# MDeckProgrammer.net
KiCad netlist of a schematic drawn in EAGLE
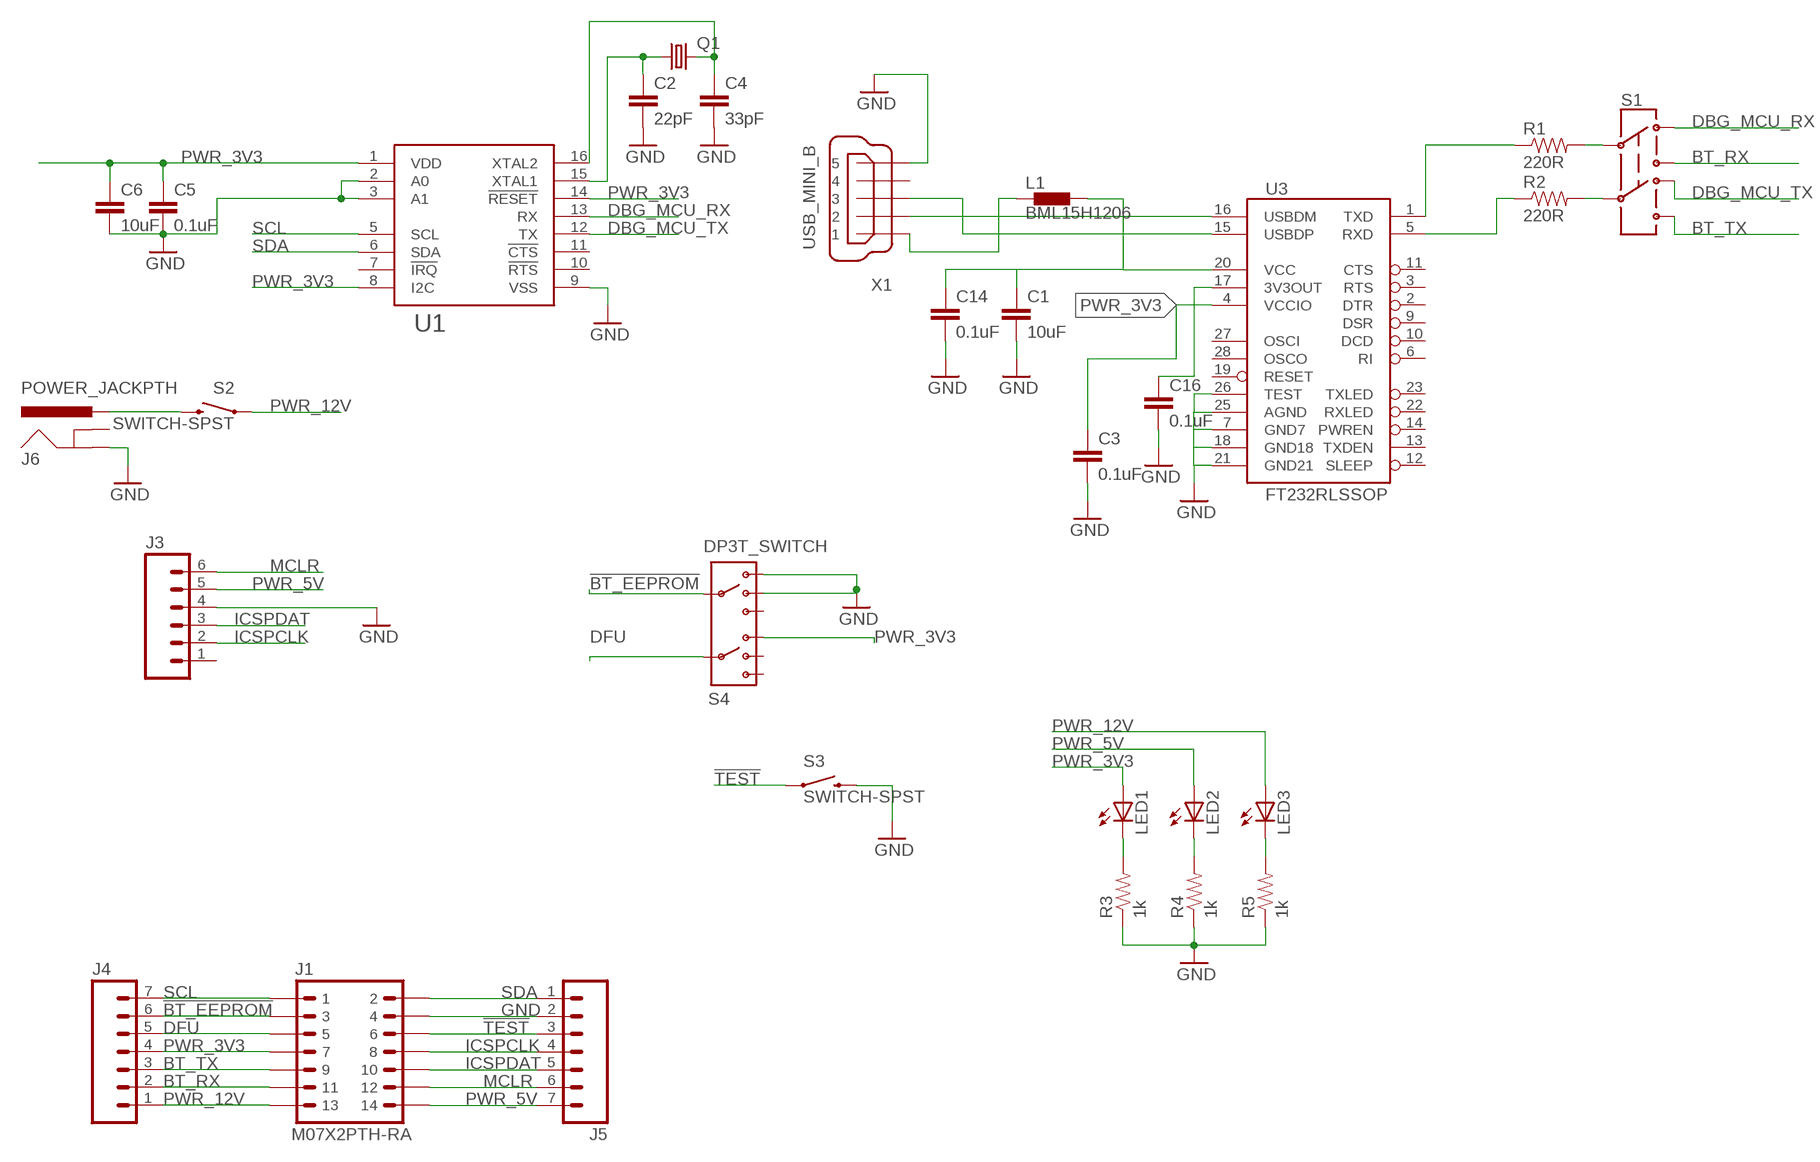
[diagram p0: schematic, sheet 1]

(export (version "E")
  (design (tool "Eeschema 10.0.6"))
  (components
    (comp (ref "C1")
      (value "10uF")
      (footprint "eagle-import:1206")
      (libsource (lib "eagle-import") (part "CAP1206"))
    )
    (comp (ref "C2")
      (value "22pF")
      (footprint "eagle-import:1206")
      (libsource (lib "eagle-import") (part "CAP1206"))
    )
    (comp (ref "C3")
      (value "0.1uF")
      (footprint "eagle-import:1206")
      (libsource (lib "eagle-import") (part "CAP1206"))
    )
    (comp (ref "C4")
      (value "33pF")
      (footprint "eagle-import:1206")
      (libsource (lib "eagle-import") (part "CAP1206"))
    )
    (comp (ref "C5")
      (value "0.1uF")
      (footprint "eagle-import:1206")
      (libsource (lib "eagle-import") (part "CAP1206"))
    )
    (comp (ref "C6")
      (value "10uF")
      (footprint "eagle-import:1206")
      (libsource (lib "eagle-import") (part "CAP1206"))
    )
    (comp (ref "C14")
      (value "0.1uF")
      (footprint "eagle-import:1206")
      (libsource (lib "eagle-import") (part "CAP1206"))
    )
    (comp (ref "C16")
      (value "0.1uF")
      (footprint "eagle-import:1206")
      (libsource (lib "eagle-import") (part "CAP1206"))
    )
    (comp (ref "J1")
      (value "M07X2PTH-RA")
      (footprint "eagle-import:JST-14-PUD-PTH")
      (libsource (lib "eagle-import") (part "M07X2PTH-RA"))
    )
    (comp (ref "J3")
      (value "M06HARWIN_RA")
      (footprint "eagle-import:1X06_RA")
      (libsource (lib "eagle-import") (part "M06HARWIN_RA"))
    )
    (comp (ref "J4")
      (value "M07")
      (footprint "eagle-import:1X07")
      (libsource (lib "eagle-import") (part "M07"))
    )
    (comp (ref "J5")
      (value "M07")
      (footprint "eagle-import:1X07")
      (libsource (lib "eagle-import") (part "M07"))
    )
    (comp (ref "J6")
      (value "POWER_JACKPTH")
      (footprint "eagle-import:POWER_JACK_PTH")
      (libsource (lib "eagle-import") (part "POWER_JACKPTH"))
    )
    (comp (ref "L1")
      (value "BML15H1206")
      (footprint "eagle-import:1206")
      (libsource (lib "eagle-import") (part "BML15H1206"))
    )
    (comp (ref "LED1")
      (value "LEDCHIPLED_1206")
      (footprint "eagle-import:CHIPLED_1206")
      (libsource (lib "eagle-import") (part "LEDCHIPLED_1206"))
    )
    (comp (ref "LED2")
      (value "LEDCHIPLED_1206")
      (footprint "eagle-import:CHIPLED_1206")
      (libsource (lib "eagle-import") (part "LEDCHIPLED_1206"))
    )
    (comp (ref "LED3")
      (value "LEDCHIPLED_1206")
      (footprint "eagle-import:CHIPLED_1206")
      (libsource (lib "eagle-import") (part "LEDCHIPLED_1206"))
    )
    (comp (ref "Q1")
      (value "CRYSTALHC49S")
      (footprint "eagle-import:HC49_S")
      (libsource (lib "eagle-import") (part "CRYSTALHC49S"))
    )
    (comp (ref "R1")
      (value "220R")
      (footprint "eagle-import:1206")
      (libsource (lib "eagle-import") (part "RESISTOR1206"))
    )
    (comp (ref "R2")
      (value "220R")
      (footprint "eagle-import:1206")
      (libsource (lib "eagle-import") (part "RESISTOR1206"))
    )
    (comp (ref "R3")
      (value "1k")
      (footprint "eagle-import:1206")
      (libsource (lib "eagle-import") (part "RESISTOR1206"))
    )
    (comp (ref "R4")
      (value "1k")
      (footprint "eagle-import:1206")
      (libsource (lib "eagle-import") (part "RESISTOR1206"))
    )
    (comp (ref "R5")
      (value "1k")
      (footprint "eagle-import:1206")
      (libsource (lib "eagle-import") (part "RESISTOR1206"))
    )
    (comp (ref "S1")
      (value "SWITCH-DPDTPTH")
      (footprint "eagle-import:MSS22")
      (libsource (lib "eagle-import") (part "SWITCH-DPDTPTH"))
    )
    (comp (ref "S2")
      (value "SWITCH-SPST")
      (footprint "eagle-import:GF-123-0054")
      (libsource (lib "eagle-import") (part "SWITCH-SPST"))
    )
    (comp (ref "S3")
      (value "SWITCH-SPST")
      (footprint "eagle-import:GF-123-0054")
      (libsource (lib "eagle-import") (part "SWITCH-SPST"))
    )
    (comp (ref "S4")
      (value "DP3T_SWITCH")
      (footprint "eagle-import:EG2301A")
      (libsource (lib "eagle-import") (part "DP3T_SWITCH"))
    )
    (comp (ref "U1")
      (value "SC16IS740TSSOP16")
      (footprint "eagle-import:TSSOP16")
      (libsource (lib "eagle-import") (part "SC16IS740TSSOP16"))
    )
    (comp (ref "U3")
      (value "FT232RLSSOP")
      (footprint "eagle-import:SSOP28DB")
      (libsource (lib "eagle-import") (part "FT232RLSSOP"))
    )
    (comp (ref "X1")
      (value "USB_MINI_B")
      (footprint "eagle-import:USB_MINI_B_PTH")
      (libsource (lib "eagle-import") (part "USB_MINI_B"))
    )
  )
  (nets
    (net (code "1") (name "/BT_RX") (class "Default")
      (node (ref "J1") (pin "P$11") (pinfunction "11_P$11") (pintype "passive"))
      (node (ref "J4") (pin "2") (pinfunction "2_2") (pintype "passive"))
      (node (ref "S1") (pin "3") (pinfunction "3_3") (pintype "bidirectional"))
    )
    (net (code "2") (name "/BT_TX") (class "Default")
      (node (ref "J1") (pin "P$9") (pinfunction "9_P$9") (pintype "passive"))
      (node (ref "J4") (pin "3") (pinfunction "3_3") (pintype "passive"))
      (node (ref "S1") (pin "6") (pinfunction "6_6") (pintype "bidirectional"))
    )
    (net (code "3") (name "/DBG_MCU_RX") (class "Default")
      (node (ref "S1") (pin "1") (pinfunction "1_1") (pintype "bidirectional"))
      (node (ref "U1") (pin "13") (pinfunction "RX_13") (pintype "bidirectional"))
    )
    (net (code "4") (name "/DBG_MCU_TX") (class "Default")
      (node (ref "S1") (pin "4") (pinfunction "4_4") (pintype "bidirectional"))
      (node (ref "U1") (pin "12") (pinfunction "TX_12") (pintype "bidirectional"))
    )
    (net (code "5") (name "/DFU") (class "Default")
      (node (ref "J1") (pin "P$5") (pinfunction "5_P$5") (pintype "passive"))
      (node (ref "J4") (pin "5") (pinfunction "5_5") (pintype "passive"))
      (node (ref "S4") (pin "P$7") (pinfunction "COMB_P$7") (pintype "passive"))
    )
    (net (code "6") (name "/ICSPCLK") (class "Default")
      (node (ref "J1") (pin "P$8") (pinfunction "8_P$8") (pintype "passive"))
      (node (ref "J3") (pin "2") (pinfunction "2_2") (pintype "passive"))
      (node (ref "J5") (pin "4") (pinfunction "4_4") (pintype "passive"))
    )
    (net (code "7") (name "/ICSPDAT") (class "Default")
      (node (ref "J1") (pin "P$10") (pinfunction "10_P$10") (pintype "passive"))
      (node (ref "J3") (pin "3") (pinfunction "3_3") (pintype "passive"))
      (node (ref "J5") (pin "5") (pinfunction "5_5") (pintype "passive"))
    )
    (net (code "8") (name "/MCLR") (class "Default")
      (node (ref "J1") (pin "P$12") (pinfunction "12_P$12") (pintype "passive"))
      (node (ref "J3") (pin "6") (pinfunction "6_6") (pintype "passive"))
      (node (ref "J5") (pin "6") (pinfunction "6_6") (pintype "passive"))
    )
    (net (code "9") (name "/PWR_5V") (class "Default")
      (node (ref "J1") (pin "P$14") (pinfunction "14_P$14") (pintype "passive"))
      (node (ref "J3") (pin "5") (pinfunction "5_5") (pintype "passive"))
      (node (ref "J5") (pin "7") (pinfunction "7_7") (pintype "passive"))
      (node (ref "LED2") (pin "A") (pinfunction "A_A") (pintype "passive"))
    )
    (net (code "10") (name "/PWR_12V") (class "Default")
      (node (ref "J1") (pin "P$13") (pinfunction "13_P$13") (pintype "passive"))
      (node (ref "J4") (pin "1") (pinfunction "1_1") (pintype "passive"))
      (node (ref "LED3") (pin "A") (pinfunction "A_A") (pintype "passive"))
      (node (ref "S2") (pin "P$1") (pinfunction "1_P$1") (pintype "passive"))
    )
    (net (code "11") (name "/SCL") (class "Default")
      (node (ref "J1") (pin "P$1") (pinfunction "1_P$1") (pintype "passive"))
      (node (ref "J4") (pin "7") (pinfunction "7_7") (pintype "passive"))
      (node (ref "U1") (pin "5") (pinfunction "SCL_5") (pintype "bidirectional"))
    )
    (net (code "12") (name "/SDA") (class "Default")
      (node (ref "J1") (pin "P$2") (pinfunction "2_P$2") (pintype "passive"))
      (node (ref "J5") (pin "1") (pinfunction "1_1") (pintype "passive"))
      (node (ref "U1") (pin "6") (pinfunction "SDA_6") (pintype "bidirectional"))
    )
    (net (code "13") (name "/~{BT_EEPROM}") (class "Default")
      (node (ref "J1") (pin "P$3") (pinfunction "3_P$3") (pintype "passive"))
      (node (ref "J4") (pin "6") (pinfunction "6_6") (pintype "passive"))
      (node (ref "S4") (pin "P$3") (pinfunction "COMA_P$3") (pintype "passive"))
    )
    (net (code "14") (name "/~{TEST}") (class "Default")
      (node (ref "J1") (pin "P$6") (pinfunction "6_P$6") (pintype "passive"))
      (node (ref "J5") (pin "3") (pinfunction "3_3") (pintype "passive"))
      (node (ref "S3") (pin "P$1") (pinfunction "1_P$1") (pintype "passive"))
    )
    (net (code "15") (name "GND") (class "Default")
      (node (ref "C1") (pin "2") (pinfunction "2_2") (pintype "passive"))
      (node (ref "C14") (pin "2") (pinfunction "2_2") (pintype "passive"))
      (node (ref "C16") (pin "2") (pinfunction "2_2") (pintype "passive"))
      (node (ref "C2") (pin "2") (pinfunction "2_2") (pintype "passive"))
      (node (ref "C3") (pin "2") (pinfunction "2_2") (pintype "passive"))
      (node (ref "C4") (pin "2") (pinfunction "2_2") (pintype "passive"))
      (node (ref "C5") (pin "2") (pinfunction "2_2") (pintype "passive"))
      (node (ref "C6") (pin "2") (pinfunction "2_2") (pintype "passive"))
      (node (ref "J1") (pin "P$4") (pinfunction "4_P$4") (pintype "passive"))
      (node (ref "J3") (pin "4") (pinfunction "4_4") (pintype "passive"))
      (node (ref "J5") (pin "2") (pinfunction "2_2") (pintype "passive"))
      (node (ref "J6") (pin "GND") (pinfunction "GND_GND") (pintype "bidirectional"))
      (node (ref "R3") (pin "1") (pinfunction "1_1") (pintype "passive"))
      (node (ref "R4") (pin "1") (pinfunction "1_1") (pintype "passive"))
      (node (ref "R5") (pin "1") (pinfunction "1_1") (pintype "passive"))
      (node (ref "S3") (pin "P$2") (pinfunction "2_P$2") (pintype "passive"))
      (node (ref "S4") (pin "P$1") (pinfunction "A1_P$1") (pintype "passive"))
      (node (ref "S4") (pin "P$2") (pinfunction "A2_P$2") (pintype "passive"))
      (node (ref "U1") (pin "2") (pinfunction "A0_2") (pintype "bidirectional"))
      (node (ref "U1") (pin "3") (pinfunction "A1_3") (pintype "bidirectional"))
      (node (ref "U1") (pin "9") (pinfunction "VSS_9") (pintype "bidirectional"))
      (node (ref "U3") (pin "18") (pinfunction "GND18_18") (pintype "power_in"))
      (node (ref "U3") (pin "21") (pinfunction "GND21_21") (pintype "power_in"))
      (node (ref "U3") (pin "25") (pinfunction "AGND_25") (pintype "power_in"))
      (node (ref "U3") (pin "26") (pinfunction "TEST_26") (pintype "input"))
      (node (ref "U3") (pin "7") (pinfunction "GND7_7") (pintype "power_in"))
      (node (ref "X1") (pin "5") (pinfunction "5_5") (pintype "passive"))
    )
    (net (code "16") (name "Net-(L1-Pad1)") (class "Default")
      (node (ref "L1") (pin "1") (pinfunction "1_1") (pintype "passive"))
      (node (ref "X1") (pin "1") (pinfunction "1_1") (pintype "passive"))
    )
    (net (code "17") (name "Net-(LED1-PadC)") (class "Default")
      (node (ref "LED1") (pin "C") (pinfunction "C_C") (pintype "passive"))
      (node (ref "R3") (pin "2") (pinfunction "2_2") (pintype "passive"))
    )
    (net (code "18") (name "Net-(LED2-PadC)") (class "Default")
      (node (ref "LED2") (pin "C") (pinfunction "C_C") (pintype "passive"))
      (node (ref "R4") (pin "2") (pinfunction "2_2") (pintype "passive"))
    )
    (net (code "19") (name "Net-(LED3-PadC)") (class "Default")
      (node (ref "LED3") (pin "C") (pinfunction "C_C") (pintype "passive"))
      (node (ref "R5") (pin "2") (pinfunction "2_2") (pintype "passive"))
    )
    (net (code "20") (name "Net-(R1-Pad2)") (class "Default")
      (node (ref "R1") (pin "2") (pinfunction "2_2") (pintype "passive"))
      (node (ref "S1") (pin "2") (pinfunction "2_2") (pintype "bidirectional"))
    )
    (net (code "21") (name "Net-(R2-Pad2)") (class "Default")
      (node (ref "R2") (pin "2") (pinfunction "2_2") (pintype "passive"))
      (node (ref "S1") (pin "5") (pinfunction "5_5") (pintype "bidirectional"))
    )
    (net (code "22") (name "Net-(S2-2)") (class "Default")
      (node (ref "J6") (pin "PWR") (pinfunction "PWR_PWR") (pintype "bidirectional"))
      (node (ref "S2") (pin "P$2") (pinfunction "2_P$2") (pintype "passive"))
    )
    (net (code "23") (name "Net-(U1-XTAL1)") (class "Default")
      (node (ref "C2") (pin "1") (pinfunction "1_1") (pintype "passive"))
      (node (ref "Q1") (pin "1") (pinfunction "1_1") (pintype "passive"))
      (node (ref "U1") (pin "15") (pinfunction "XTAL1_15") (pintype "bidirectional"))
    )
    (net (code "24") (name "Net-(U1-XTAL2)") (class "Default")
      (node (ref "C4") (pin "1") (pinfunction "1_1") (pintype "passive"))
      (node (ref "Q1") (pin "2") (pinfunction "2_2") (pintype "passive"))
      (node (ref "U1") (pin "16") (pinfunction "XTAL2_16") (pintype "bidirectional"))
    )
    (net (code "25") (name "Net-(U3-3V3OUT)") (class "Default")
      (node (ref "C16") (pin "1") (pinfunction "1_1") (pintype "passive"))
      (node (ref "U3") (pin "17") (pinfunction "3V3OUT_17") (pintype "output"))
    )
    (net (code "26") (name "Net-(U3-RXD)") (class "Default")
      (node (ref "R2") (pin "1") (pinfunction "1_1") (pintype "passive"))
      (node (ref "U3") (pin "5") (pinfunction "RXD_5") (pintype "input"))
    )
    (net (code "27") (name "Net-(U3-TXD)") (class "Default")
      (node (ref "R1") (pin "1") (pinfunction "1_1") (pintype "passive"))
      (node (ref "U3") (pin "1") (pinfunction "TXD_1") (pintype "output"))
    )
    (net (code "28") (name "Net-(U3-USBDM)") (class "Default")
      (node (ref "U3") (pin "16") (pinfunction "USBDM_16") (pintype "bidirectional"))
      (node (ref "X1") (pin "2") (pinfunction "2_2") (pintype "passive"))
    )
    (net (code "29") (name "Net-(U3-USBDP)") (class "Default")
      (node (ref "U3") (pin "15") (pinfunction "USBDP_15") (pintype "bidirectional"))
      (node (ref "X1") (pin "3") (pinfunction "3_3") (pintype "passive"))
    )
    (net (code "30") (name "Net-(U3-VCC)") (class "Default")
      (node (ref "C1") (pin "1") (pinfunction "1_1") (pintype "passive"))
      (node (ref "C14") (pin "1") (pinfunction "1_1") (pintype "passive"))
      (node (ref "L1") (pin "2") (pinfunction "2_2") (pintype "passive"))
      (node (ref "U3") (pin "20") (pinfunction "VCC_20") (pintype "power_in"))
    )
    (net (code "31") (name "PWR_3V3") (class "Default")
      (node (ref "C3") (pin "1") (pinfunction "1_1") (pintype "passive"))
      (node (ref "C5") (pin "1") (pinfunction "1_1") (pintype "passive"))
      (node (ref "C6") (pin "1") (pinfunction "1_1") (pintype "passive"))
      (node (ref "J1") (pin "P$7") (pinfunction "7_P$7") (pintype "passive"))
      (node (ref "J4") (pin "4") (pinfunction "4_4") (pintype "passive"))
      (node (ref "LED1") (pin "A") (pinfunction "A_A") (pintype "passive"))
      (node (ref "S4") (pin "P$5") (pinfunction "B1_P$5") (pintype "passive"))
      (node (ref "U1") (pin "1") (pinfunction "VDD_1") (pintype "bidirectional"))
      (node (ref "U1") (pin "14") (pinfunction "~{RESET}_14") (pintype "bidirectional"))
      (node (ref "U1") (pin "8") (pinfunction "I2C_8") (pintype "bidirectional"))
      (node (ref "U3") (pin "4") (pinfunction "VCCIO_4") (pintype "power_in"))
    )
    (net (code "32") (name "unconnected-(J3-Pad1)") (class "Default")
      (node (ref "J3") (pin "1") (pinfunction "1_1") (pintype "passive"))
    )
    (net (code "33") (name "unconnected-(J6-PadGNDBREAK)") (class "Default")
      (node (ref "J6") (pin "GNDBREAK") (pinfunction "GNDBREAK_GNDBREAK") (pintype "bidirectional"))
    )
    (net (code "34") (name "unconnected-(S4-A3-PadP$4)") (class "Default")
      (node (ref "S4") (pin "P$4") (pinfunction "A3_P$4") (pintype "passive"))
    )
    (net (code "35") (name "unconnected-(S4-B2-PadP$6)") (class "Default")
      (node (ref "S4") (pin "P$6") (pinfunction "B2_P$6") (pintype "passive"))
    )
    (net (code "36") (name "unconnected-(S4-B3-PadP$8)") (class "Default")
      (node (ref "S4") (pin "P$8") (pinfunction "B3_P$8") (pintype "passive"))
    )
    (net (code "37") (name "unconnected-(U1-~{CTS}-Pad11)") (class "Default")
      (node (ref "U1") (pin "11") (pinfunction "~{CTS}_11") (pintype "bidirectional"))
    )
    (net (code "38") (name "unconnected-(U1-~{IRQ}-Pad7)") (class "Default")
      (node (ref "U1") (pin "7") (pinfunction "~{IRQ}_7") (pintype "bidirectional"))
    )
    (net (code "39") (name "unconnected-(U1-~{RTS}-Pad10)") (class "Default")
      (node (ref "U1") (pin "10") (pinfunction "~{RTS}_10") (pintype "bidirectional"))
    )
    (net (code "40") (name "unconnected-(U3-CTS-Pad11)") (class "Default")
      (node (ref "U3") (pin "11") (pinfunction "CTS_11") (pintype "input"))
    )
    (net (code "41") (name "unconnected-(U3-DCD-Pad10)") (class "Default")
      (node (ref "U3") (pin "10") (pinfunction "DCD_10") (pintype "input"))
    )
    (net (code "42") (name "unconnected-(U3-DSR-Pad9)") (class "Default")
      (node (ref "U3") (pin "9") (pinfunction "DSR_9") (pintype "input"))
    )
    (net (code "43") (name "unconnected-(U3-DTR-Pad2)") (class "Default")
      (node (ref "U3") (pin "2") (pinfunction "DTR_2") (pintype "output"))
    )
    (net (code "44") (name "unconnected-(U3-OSCI-Pad27)") (class "Default")
      (node (ref "U3") (pin "27") (pinfunction "OSCI_27") (pintype "input"))
    )
    (net (code "45") (name "unconnected-(U3-OSCO-Pad28)") (class "Default")
      (node (ref "U3") (pin "28") (pinfunction "OSCO_28") (pintype "output"))
    )
    (net (code "46") (name "unconnected-(U3-PWREN-Pad14)") (class "Default")
      (node (ref "U3") (pin "14") (pinfunction "PWREN_14") (pintype "input"))
    )
    (net (code "47") (name "unconnected-(U3-RESET-Pad19)") (class "Default")
      (node (ref "U3") (pin "19") (pinfunction "RESET_19") (pintype "input"))
    )
    (net (code "48") (name "unconnected-(U3-RI-Pad6)") (class "Default")
      (node (ref "U3") (pin "6") (pinfunction "RI_6") (pintype "input"))
    )
    (net (code "49") (name "unconnected-(U3-RTS-Pad3)") (class "Default")
      (node (ref "U3") (pin "3") (pinfunction "RTS_3") (pintype "output"))
    )
    (net (code "50") (name "unconnected-(U3-RXLED-Pad22)") (class "Default")
      (node (ref "U3") (pin "22") (pinfunction "RXLED_22") (pintype "input"))
    )
    (net (code "51") (name "unconnected-(U3-SLEEP-Pad12)") (class "Default")
      (node (ref "U3") (pin "12") (pinfunction "SLEEP_12") (pintype "input"))
    )
    (net (code "52") (name "unconnected-(U3-TXDEN-Pad13)") (class "Default")
      (node (ref "U3") (pin "13") (pinfunction "TXDEN_13") (pintype "input"))
    )
    (net (code "53") (name "unconnected-(U3-TXLED-Pad23)") (class "Default")
      (node (ref "U3") (pin "23") (pinfunction "TXLED_23") (pintype "input"))
    )
    (net (code "54") (name "unconnected-(X1-Pad4)") (class "Default")
      (node (ref "X1") (pin "4") (pinfunction "4_4") (pintype "passive"))
    )
  )
)
